# lora.net
KiCad netlist of a schematic drawn in Altium Designer
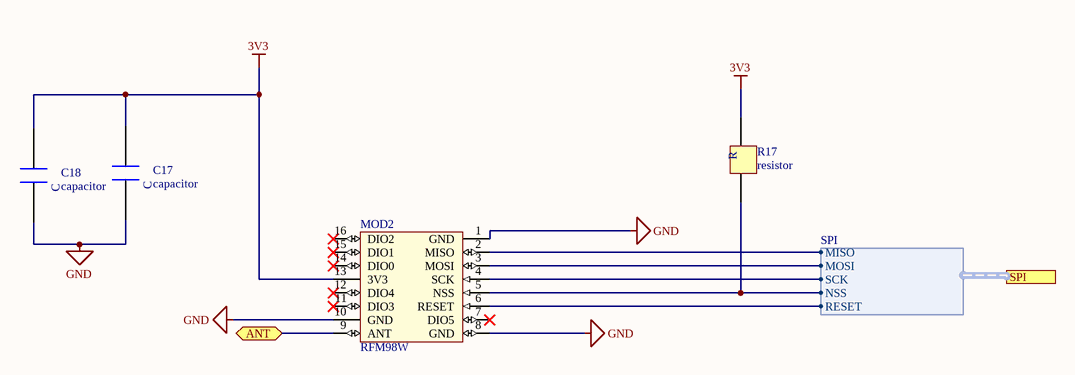
[diagram p0: lora.SchDoc]

(export (version "E")
  (design (tool "Eeschema 10.0.6"))
  (components
    (comp (ref "C17")
      (value "capacitor")
      (footprint "CAPC1005X04L")
      (libsource (lib "pasives") (part "capacitor"))
    )
    (comp (ref "C18")
      (value "capacitor")
      (footprint "CAPC1005X04L")
      (libsource (lib "pasives") (part "capacitor"))
    )
    (comp (ref "MOD2") (value "RFM98W") (libsource (lib "halfgelijders") (part "RFM98W")))
    (comp (ref "R17")
      (value "resistor")
      (footprint "CAPC1005X04L")
      (libsource (lib "pasives") (part "resistor"))
    )
  )
  (nets
    (net (code "2") (name "/ANT") (class "Default")
      (node (ref "MOD2") (pin "9") (pinfunction "ANT_9") (pintype "bidirectional"))
    )
    (net (code "3") (name "/MISO") (class "Default")
      (node (ref "MOD2") (pin "2") (pinfunction "MISO_2") (pintype "bidirectional"))
    )
    (net (code "4") (name "/MOSI") (class "Default")
      (node (ref "MOD2") (pin "3") (pinfunction "MOSI_3") (pintype "bidirectional"))
    )
    (net (code "5") (name "/NSS") (class "Default")
      (node (ref "MOD2") (pin "5") (pinfunction "NSS_5") (pintype "input"))
      (node (ref "R17") (pin "2") (pinfunction "2_2") (pintype "passive"))
    )
    (net (code "6") (name "/RESET") (class "Default")
      (node (ref "MOD2") (pin "6") (pinfunction "RESET_6") (pintype "input"))
    )
    (net (code "7") (name "/SCK") (class "Default")
      (node (ref "MOD2") (pin "4") (pinfunction "SCK_4") (pintype "input"))
    )
    (net (code "9") (name "3V3") (class "Default")
      (node (ref "C17") (pin "1") (pinfunction "1_1") (pintype "passive"))
      (node (ref "C18") (pin "1") (pinfunction "1_1") (pintype "passive"))
      (node (ref "MOD2") (pin "13") (pinfunction "3V3_13") (pintype "power_in"))
      (node (ref "R17") (pin "1") (pinfunction "1_1") (pintype "passive"))
    )
    (net (code "10") (name "GND") (class "Default")
      (node (ref "C17") (pin "2") (pinfunction "2_2") (pintype "passive"))
      (node (ref "C18") (pin "2") (pinfunction "2_2") (pintype "passive"))
      (node (ref "MOD2") (pin "1") (pinfunction "GND_1") (pintype "power_in"))
      (node (ref "MOD2") (pin "10") (pinfunction "GND_10") (pintype "power_in"))
      (node (ref "MOD2") (pin "8") (pinfunction "GND_8") (pintype "bidirectional"))
    )
    (net (code "11") (name "unconnected-(MOD2-DIO0-Pad14)") (class "Default")
      (node (ref "MOD2") (pin "14") (pinfunction "DIO0_14") (pintype "bidirectional+no_connect"))
    )
    (net (code "12") (name "unconnected-(MOD2-DIO1-Pad15)") (class "Default")
      (node (ref "MOD2") (pin "15") (pinfunction "DIO1_15") (pintype "bidirectional+no_connect"))
    )
    (net (code "13") (name "unconnected-(MOD2-DIO2-Pad16)") (class "Default")
      (node (ref "MOD2") (pin "16") (pinfunction "DIO2_16") (pintype "bidirectional+no_connect"))
    )
    (net (code "14") (name "unconnected-(MOD2-DIO3-Pad11)") (class "Default")
      (node (ref "MOD2") (pin "11") (pinfunction "DIO3_11") (pintype "bidirectional+no_connect"))
    )
    (net (code "15") (name "unconnected-(MOD2-DIO4-Pad12)") (class "Default")
      (node (ref "MOD2") (pin "12") (pinfunction "DIO4_12") (pintype "bidirectional+no_connect"))
    )
    (net (code "16") (name "unconnected-(MOD2-DIO5-Pad7)") (class "Default")
      (node (ref "MOD2") (pin "7") (pinfunction "DIO5_7") (pintype "bidirectional+no_connect"))
    )
  )
)
